# RemoteShutter1.net
KiCad netlist of a schematic drawn in Altium Designer
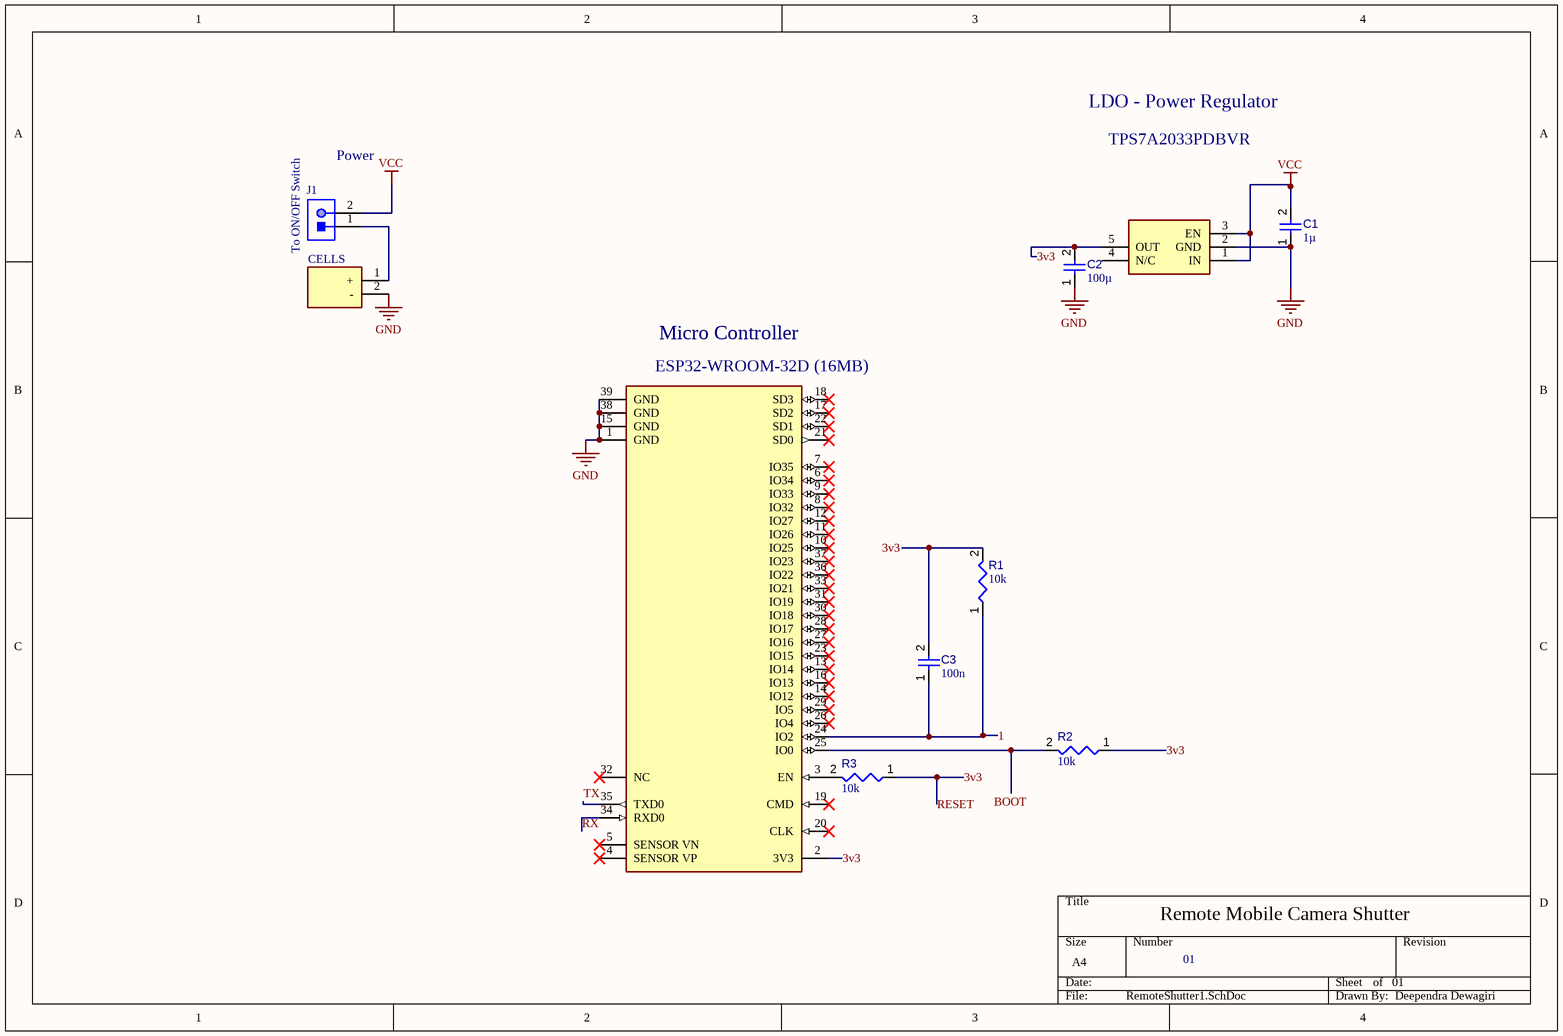
[diagram p0: RemoteShutter1.SchDoc]

(export (version "E")
  (design (tool "Eeschema 10.0.6"))
  (components
    (comp (ref "C1")
      (value "1µ")
      (footprint "CAPC2013X145X50ML20T25")
      (description "Chip Capacitor, 1 uF, +/-10%, 25 V, 0805 (2012 Metric)")
      (fields (field (name "TOLERANCE") "10%") (field (name "Comment") "Capacitor 1 uF +/- 10% 25 V 0805"))
      (libsource (lib "University of Moratuwa") (part "CAP-NP-2"))
    )
    (comp (ref "C2")
      (value "100µ")
      (footprint "CAPC0805(2012)145_L")
      (description "Chip Capacitor, 100µF +/-20%, 6.3V, 0805, Thickness 1.45 mm")
      (fields (field (name "TOLERANCE") "10%") (field (name "Comment") "Capacitor 100µF +/-20% 6.3V 0805"))
      (libsource (lib "University of Moratuwa") (part "CAP-NP-2"))
    )
    (comp (ref "C3")
      (value "100n")
      (footprint "CAPC2013X95X50LL10T25")
      (description "Chip Capacitor, 100 nF, +/- 10%, 50 V, 0805 (2012 Metric)")
      (fields (field (name "TOLERANCE") "10%"))
      (libsource (lib "University of Moratuwa") (part "CAP-NP-2"))
    )
    (comp (ref "CELLS")
      (value "1062")
      (footprint "SamacSys:1062")
      (description "Battery")
      (fields (field (name "MOUSER PART NUMBER") "534-1062"))
      (libsource (lib "*") (part "1062"))
    )
    (comp (ref "ESP32-WROOM-32D (16MB)")
      (value "ESP32-WROOM-32D (16MB)")
      (footprint "FP-ESP32-WROOM-32D_16MB-MFG")
      (description "RX TXRX MOD WIFI TRACE ANT SMD")
      (libsource (lib "Altium Content Vault") (part "0f6efa1e107731c2e5e3f960d62f5e3"))
    )
    (comp (ref "J1")
      (value "61300211121")
      (footprint "61300211121")
      (description "THT Vertical Pin Header WR-PHD, Pitch 2.54 mm, Single Row, 2 pins")
      (fields (field (name "MANUFACTURER") "Wurth Elektronik") (field (name "PUBLISHER") "WurthElektronik"))
      (libsource (lib "Altium Content Vault") (part "WE-CN-1P-M-R2"))
    )
    (comp (ref "R1")
      (value "10k")
      (footprint "RESC2013X50X35ML15T15")
      (description "Chip Resistor, 10 KOhm, +/- 1%, 125 mW, -55 to 155 degC, 0805 (2012 Metric)")
      (fields (field (name "TOLERANCE") "1%") (field (name "POWER") "125mW"))
      (libsource (lib "University of Moratuwa") (part "RES-2"))
    )
    (comp (ref "R2")
      (value "10k")
      (footprint "RESC2013X50X35ML15T15")
      (description "Chip Resistor, 10 KOhm, +/- 1%, 125 mW, -55 to 155 degC, 0805 (2012 Metric)")
      (fields (field (name "TOLERANCE") "1%") (field (name "POWER") "125mW"))
      (libsource (lib "University of Moratuwa") (part "RES-2"))
    )
    (comp (ref "R3")
      (value "10k")
      (footprint "RESC2013X50X35ML15T15")
      (description "Chip Resistor, 10 KOhm, +/- 1%, 125 mW, -55 to 155 degC, 0805 (2012 Metric)")
      (fields (field (name "TOLERANCE") "1%") (field (name "POWER") "125mW"))
      (libsource (lib "University of Moratuwa") (part "RES-2"))
    )
    (comp (ref "TPS7A2033PDBVR")
      (value "TPS7A2033PDBVR")
      (footprint "SOT95P280X145-5N")
      (description "300-mA, Ultra-Low-Noise, Low-IQ, High PSRR LDO")
      (fields (field (name "MOUSER PART NUMBER") "595-TPS7A2033PDBVR"))
      (libsource (lib "University of Moratuwa") (part "TPS7A2033PDBVR"))
    )
  )
  (nets
    (net (code "1") (name "/1") (class "Default")
      (node (ref "C3") (pin "1") (pinfunction "1_1") (pintype "passive"))
      (node (ref "ESP32-WROOM-32D (16MB)") (pin "24") (pinfunction "IO2_24") (pintype "bidirectional"))
      (node (ref "R1") (pin "1") (pinfunction "1_1") (pintype "passive"))
    )
    (net (code "2") (name "/3v3") (class "Default")
      (node (ref "C2") (pin "2") (pinfunction "2_2") (pintype "passive"))
      (node (ref "C3") (pin "2") (pinfunction "2_2") (pintype "passive"))
      (node (ref "ESP32-WROOM-32D (16MB)") (pin "2") (pinfunction "3V3_2") (pintype "power_in"))
      (node (ref "R1") (pin "2") (pinfunction "2_2") (pintype "passive"))
      (node (ref "R2") (pin "1") (pinfunction "1_1") (pintype "passive"))
      (node (ref "R3") (pin "1") (pinfunction "1_1") (pintype "passive"))
      (node (ref "TPS7A2033PDBVR") (pin "5") (pinfunction "OUT_5") (pintype "passive"))
    )
    (net (code "3") (name "/BOOT") (class "Default")
      (node (ref "ESP32-WROOM-32D (16MB)") (pin "25") (pinfunction "IO0_25") (pintype "bidirectional"))
      (node (ref "R2") (pin "2") (pinfunction "2_2") (pintype "passive"))
    )
    (net (code "4") (name "/RX") (class "Default")
      (node (ref "ESP32-WROOM-32D (16MB)") (pin "34") (pinfunction "RXD0_34") (pintype "input"))
    )
    (net (code "5") (name "/TX") (class "Default")
      (node (ref "ESP32-WROOM-32D (16MB)") (pin "35") (pinfunction "TXD0_35") (pintype "output"))
    )
    (net (code "6") (name "GND") (class "Default")
      (node (ref "C1") (pin "1") (pinfunction "1_1") (pintype "passive"))
      (node (ref "C2") (pin "1") (pinfunction "1_1") (pintype "passive"))
      (node (ref "CELLS") (pin "2") (pinfunction "-_2") (pintype "passive"))
      (node (ref "ESP32-WROOM-32D (16MB)") (pin "1") (pinfunction "GND_1") (pintype "power_in"))
      (node (ref "ESP32-WROOM-32D (16MB)") (pin "15") (pinfunction "GND_15") (pintype "power_in"))
      (node (ref "ESP32-WROOM-32D (16MB)") (pin "38") (pinfunction "GND_38") (pintype "power_in"))
      (node (ref "ESP32-WROOM-32D (16MB)") (pin "39") (pinfunction "GND_39") (pintype "power_in"))
      (node (ref "TPS7A2033PDBVR") (pin "2") (pinfunction "GND_2") (pintype "passive"))
    )
    (net (code "7") (name "Net-(CELLS-+)") (class "Default")
      (node (ref "CELLS") (pin "1") (pinfunction "+_1") (pintype "passive"))
      (node (ref "J1") (pin "1") (pinfunction "1_1") (pintype "passive"))
    )
    (net (code "8") (name "Net-(ESP32-WROOM-32D (16MB)-EN)") (class "Default")
      (node (ref "ESP32-WROOM-32D (16MB)") (pin "3") (pinfunction "EN_3") (pintype "input"))
      (node (ref "R3") (pin "2") (pinfunction "2_2") (pintype "passive"))
    )
    (net (code "9") (name "VCC") (class "Default")
      (node (ref "C1") (pin "2") (pinfunction "2_2") (pintype "passive"))
      (node (ref "J1") (pin "2") (pinfunction "2_2") (pintype "passive"))
      (node (ref "TPS7A2033PDBVR") (pin "1") (pinfunction "IN_1") (pintype "passive"))
      (node (ref "TPS7A2033PDBVR") (pin "3") (pinfunction "EN_3") (pintype "passive"))
    )
    (net (code "10") (name "unconnected-(ESP32-WROOM-32D (16MB)-CLK-Pad20)") (class "Default")
      (node (ref "ESP32-WROOM-32D (16MB)") (pin "20") (pinfunction "CLK_20") (pintype "input+no_connect"))
    )
    (net (code "11") (name "unconnected-(ESP32-WROOM-32D (16MB)-CMD-Pad19)") (class "Default")
      (node (ref "ESP32-WROOM-32D (16MB)") (pin "19") (pinfunction "CMD_19") (pintype "input+no_connect"))
    )
    (net (code "12") (name "unconnected-(ESP32-WROOM-32D (16MB)-IO4-Pad26)") (class "Default")
      (node (ref "ESP32-WROOM-32D (16MB)") (pin "26") (pinfunction "IO4_26") (pintype "bidirectional+no_connect"))
    )
    (net (code "13") (name "unconnected-(ESP32-WROOM-32D (16MB)-IO5-Pad29)") (class "Default")
      (node (ref "ESP32-WROOM-32D (16MB)") (pin "29") (pinfunction "IO5_29") (pintype "bidirectional+no_connect"))
    )
    (net (code "14") (name "unconnected-(ESP32-WROOM-32D (16MB)-IO12-Pad14)") (class "Default")
      (node (ref "ESP32-WROOM-32D (16MB)") (pin "14") (pinfunction "IO12_14") (pintype "bidirectional+no_connect"))
    )
    (net (code "15") (name "unconnected-(ESP32-WROOM-32D (16MB)-IO13-Pad16)") (class "Default")
      (node (ref "ESP32-WROOM-32D (16MB)") (pin "16") (pinfunction "IO13_16") (pintype "bidirectional+no_connect"))
    )
    (net (code "16") (name "unconnected-(ESP32-WROOM-32D (16MB)-IO14-Pad13)") (class "Default")
      (node (ref "ESP32-WROOM-32D (16MB)") (pin "13") (pinfunction "IO14_13") (pintype "bidirectional+no_connect"))
    )
    (net (code "17") (name "unconnected-(ESP32-WROOM-32D (16MB)-IO15-Pad23)") (class "Default")
      (node (ref "ESP32-WROOM-32D (16MB)") (pin "23") (pinfunction "IO15_23") (pintype "bidirectional+no_connect"))
    )
    (net (code "18") (name "unconnected-(ESP32-WROOM-32D (16MB)-IO16-Pad27)") (class "Default")
      (node (ref "ESP32-WROOM-32D (16MB)") (pin "27") (pinfunction "IO16_27") (pintype "bidirectional+no_connect"))
    )
    (net (code "19") (name "unconnected-(ESP32-WROOM-32D (16MB)-IO17-Pad28)") (class "Default")
      (node (ref "ESP32-WROOM-32D (16MB)") (pin "28") (pinfunction "IO17_28") (pintype "bidirectional+no_connect"))
    )
    (net (code "20") (name "unconnected-(ESP32-WROOM-32D (16MB)-IO18-Pad30)") (class "Default")
      (node (ref "ESP32-WROOM-32D (16MB)") (pin "30") (pinfunction "IO18_30") (pintype "bidirectional+no_connect"))
    )
    (net (code "21") (name "unconnected-(ESP32-WROOM-32D (16MB)-IO19-Pad31)") (class "Default")
      (node (ref "ESP32-WROOM-32D (16MB)") (pin "31") (pinfunction "IO19_31") (pintype "bidirectional+no_connect"))
    )
    (net (code "22") (name "unconnected-(ESP32-WROOM-32D (16MB)-IO21-Pad33)") (class "Default")
      (node (ref "ESP32-WROOM-32D (16MB)") (pin "33") (pinfunction "IO21_33") (pintype "bidirectional+no_connect"))
    )
    (net (code "23") (name "unconnected-(ESP32-WROOM-32D (16MB)-IO22-Pad36)") (class "Default")
      (node (ref "ESP32-WROOM-32D (16MB)") (pin "36") (pinfunction "IO22_36") (pintype "bidirectional+no_connect"))
    )
    (net (code "24") (name "unconnected-(ESP32-WROOM-32D (16MB)-IO23-Pad37)") (class "Default")
      (node (ref "ESP32-WROOM-32D (16MB)") (pin "37") (pinfunction "IO23_37") (pintype "bidirectional+no_connect"))
    )
    (net (code "25") (name "unconnected-(ESP32-WROOM-32D (16MB)-IO25-Pad10)") (class "Default")
      (node (ref "ESP32-WROOM-32D (16MB)") (pin "10") (pinfunction "IO25_10") (pintype "bidirectional+no_connect"))
    )
    (net (code "26") (name "unconnected-(ESP32-WROOM-32D (16MB)-IO26-Pad11)") (class "Default")
      (node (ref "ESP32-WROOM-32D (16MB)") (pin "11") (pinfunction "IO26_11") (pintype "bidirectional+no_connect"))
    )
    (net (code "27") (name "unconnected-(ESP32-WROOM-32D (16MB)-IO27-Pad12)") (class "Default")
      (node (ref "ESP32-WROOM-32D (16MB)") (pin "12") (pinfunction "IO27_12") (pintype "bidirectional+no_connect"))
    )
    (net (code "28") (name "unconnected-(ESP32-WROOM-32D (16MB)-IO32-Pad8)") (class "Default")
      (node (ref "ESP32-WROOM-32D (16MB)") (pin "8") (pinfunction "IO32_8") (pintype "bidirectional+no_connect"))
    )
    (net (code "29") (name "unconnected-(ESP32-WROOM-32D (16MB)-IO33-Pad9)") (class "Default")
      (node (ref "ESP32-WROOM-32D (16MB)") (pin "9") (pinfunction "IO33_9") (pintype "bidirectional+no_connect"))
    )
    (net (code "30") (name "unconnected-(ESP32-WROOM-32D (16MB)-IO34-Pad6)") (class "Default")
      (node (ref "ESP32-WROOM-32D (16MB)") (pin "6") (pinfunction "IO34_6") (pintype "bidirectional+no_connect"))
    )
    (net (code "31") (name "unconnected-(ESP32-WROOM-32D (16MB)-IO35-Pad7)") (class "Default")
      (node (ref "ESP32-WROOM-32D (16MB)") (pin "7") (pinfunction "IO35_7") (pintype "bidirectional+no_connect"))
    )
    (net (code "32") (name "unconnected-(ESP32-WROOM-32D (16MB)-NC-Pad32)") (class "Default")
      (node (ref "ESP32-WROOM-32D (16MB)") (pin "32") (pinfunction "NC_32") (pintype "passive+no_connect"))
    )
    (net (code "33") (name "unconnected-(ESP32-WROOM-32D (16MB)-SD0-Pad21)") (class "Default")
      (node (ref "ESP32-WROOM-32D (16MB)") (pin "21") (pinfunction "SD0_21") (pintype "output+no_connect"))
    )
    (net (code "34") (name "unconnected-(ESP32-WROOM-32D (16MB)-SD1-Pad22)") (class "Default")
      (node (ref "ESP32-WROOM-32D (16MB)") (pin "22") (pinfunction "SD1_22") (pintype "bidirectional+no_connect"))
    )
    (net (code "35") (name "unconnected-(ESP32-WROOM-32D (16MB)-SD2-Pad17)") (class "Default")
      (node (ref "ESP32-WROOM-32D (16MB)") (pin "17") (pinfunction "SD2_17") (pintype "bidirectional+no_connect"))
    )
    (net (code "36") (name "unconnected-(ESP32-WROOM-32D (16MB)-SD3-Pad18)") (class "Default")
      (node (ref "ESP32-WROOM-32D (16MB)") (pin "18") (pinfunction "SD3_18") (pintype "bidirectional+no_connect"))
    )
    (net (code "37") (name "unconnected-(ESP32-WROOM-32D (16MB)-SENSOR_VN-Pad5)") (class "Default")
      (node (ref "ESP32-WROOM-32D (16MB)") (pin "5") (pinfunction "SENSOR_VN_5") (pintype "passive+no_connect"))
    )
    (net (code "38") (name "unconnected-(ESP32-WROOM-32D (16MB)-SENSOR_VP-Pad4)") (class "Default")
      (node (ref "ESP32-WROOM-32D (16MB)") (pin "4") (pinfunction "SENSOR_VP_4") (pintype "passive+no_connect"))
    )
    (net (code "39") (name "unconnected-(TPS7A2033PDBVR-N{slash}C-Pad4)") (class "Default")
      (node (ref "TPS7A2033PDBVR") (pin "4") (pinfunction "N/C_4") (pintype "passive"))
    )
  )
)
